# Arduino_extension_connectors.net
KiCad netlist of a schematic drawn in Altium Designer
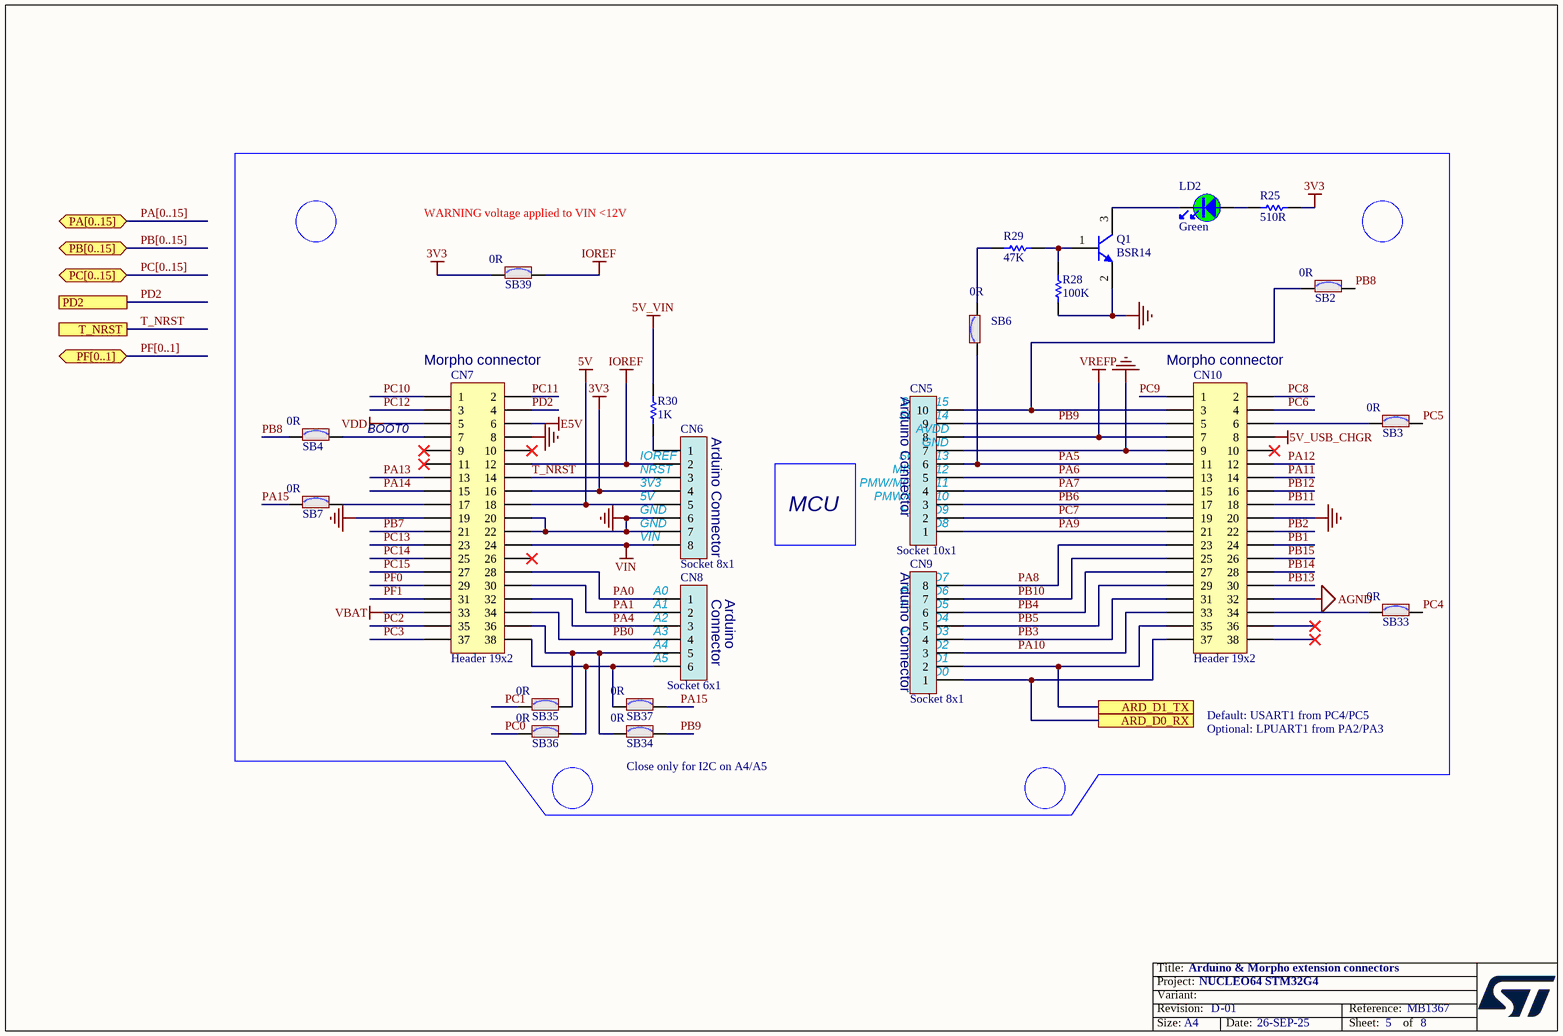
[diagram p0: Arduino_extension_connectors.SchDoc]

(export (version "E")
  (design (tool "Eeschema 10.0.6"))
  (components
    (comp (ref "CN5")
      (value "Socket 10x1")
      (footprint "CON_SAMTEC_SSW-110-03-X-S")
      (description "Socket, 10x1, 2.54mm, VR, TH, Height 8.51mm/10mm")
      (fields
        (field (name "INTERNAL_PART_NUMBER") "MCD-00262")
        (field (name "MANUFACTURER_PART_NUMBER") "SSW-110-03-G-S")
        (field (name "PROVIDED_BY") "SUBCO")
      )
      (libsource (lib "MCD_PARTS_database") (part "Socket 10x1"))
    )
    (comp (ref "CN6")
      (value "Socket 8x1")
      (footprint "CON_SAMTEC_SSW-108-03-X-S")
      (description "Socket, 8x1, 2.54mm, VR, TH, Height 8.51mm/10mm")
      (fields
        (field (name "INTERNAL_PART_NUMBER") "MCD-00261")
        (field (name "MANUFACTURER_PART_NUMBER") "SSW-108-03-G-S")
        (field (name "PROVIDED_BY") "SUBCO")
      )
      (libsource (lib "") (part "Socket 8x1_1"))
    )
    (comp (ref "CN7")
      (value "Header 19x2")
      (footprint "CON_SAMTEC_TSW-119-09-X-D")
      (description "Header, 19x2, 2,54mm, VR, TH, Height 5.84mm/10.16mm")
      (fields
        (field (name "INTERNAL_PART_NUMBER") "MCD-00213")
        (field (name "MANUFACTURER_PART_NUMBER") "TSW-119-09-G-D")
        (field (name "PROVIDED_BY") "SUBCO")
      )
      (libsource (lib "MCD_PARTS_database") (part "Header 19x2"))
    )
    (comp (ref "CN8")
      (value "Socket 6x1")
      (footprint "CON_SAMTEC_SSW-106-03-X-S")
      (description "Socket, 6x1, 2.54mm, VR, TH, Height 8.51mm/10mm")
      (fields
        (field (name "INTERNAL_PART_NUMBER") "MCD-00260")
        (field (name "MANUFACTURER_PART_NUMBER") "SSW-106-03-G-S")
        (field (name "PROVIDED_BY") "SUBCO")
      )
      (libsource (lib "MCD_PARTS_database") (part "Socket 6x1"))
    )
    (comp (ref "CN9")
      (value "Socket 8x1")
      (footprint "CON_SAMTEC_SSW-108-03-X-S")
      (description "Socket, 8x1, 2.54mm, VR, TH, Height 8.51mm/10mm")
      (fields
        (field (name "INTERNAL_PART_NUMBER") "MCD-00261")
        (field (name "MANUFACTURER_PART_NUMBER") "SSW-108-03-G-S")
        (field (name "PROVIDED_BY") "SUBCO")
      )
      (libsource (lib "MCD_PARTS_database") (part "Socket 8x1"))
    )
    (comp (ref "CN10")
      (value "Header 19x2")
      (footprint "CON_SAMTEC_TSW-119-09-X-D")
      (description "Header, 19x2, 2,54mm, VR, TH, Height 5.84mm/10.16mm")
      (fields
        (field (name "INTERNAL_PART_NUMBER") "MCD-00213")
        (field (name "MANUFACTURER_PART_NUMBER") "TSW-119-09-G-D")
        (field (name "PROVIDED_BY") "SUBCO")
      )
      (libsource (lib "MCD_PARTS_database") (part "Header 19x2"))
    )
    (comp (ref "LD2")
      (value "Green")
      (footprint "LED_0603_GREEN")
      (description "LED, Green, 2V, 20mA, 0603")
      (fields (field (name "INTERNAL_PART_NUMBER") "MCD-02900") (field (name "MANUFACTURER") "EVERLIGHT"))
      (libsource (lib "MCD_PARTS_database") (part "LED_green"))
    )
    (comp (ref "Q1")
      (value "BSR14")
      (footprint "NPN_SOT23")
      (description "NPN Bipolar Transistor")
      (fields
        (field (name "INTERNAL_PART_NUMBER") "MCD-00073")
        (field (name "MANUFACTURER") "ON SEMICONDUCTOR")
        (field (name "PROVIDED_BY") "SUBCO")
      )
      (libsource (lib "MCD_PARTS_database") (part "9013-SOT23"))
    )
    (comp (ref "R25")
      (value "510R")
      (footprint "R0603")
      (description "Resistor,510R,0603,1%,1/10W")
      (fields
        (field (name "INTERNAL_PART_NUMBER") "MCD-00225")
        (field (name "MANUFACTURER_PART_NUMBER") "RC0603FR-07510RL")
        (field (name "PROVIDED_BY") "SUBCO")
      )
      (libsource (lib "MCD_PARTS_database") (part "Resistor"))
    )
    (comp (ref "R28")
      (value "100K")
      (footprint "R0603")
      (description "Resistor,100K,0603,1%,1/10W")
      (fields
        (field (name "INTERNAL_PART_NUMBER") "MCD-00223")
        (field (name "MANUFACTURER_PART_NUMBER") "RC0603FR-07100KL")
        (field (name "PROVIDED_BY") "Subcon")
      )
      (libsource (lib "MCD_PARTS_database") (part "Resistor"))
    )
    (comp (ref "R29")
      (value "47K")
      (footprint "R0603")
      (description "Resistor,47K,0603,1%,1/10W")
      (fields
        (field (name "INTERNAL_PART_NUMBER") "MCD-00222")
        (field (name "MANUFACTURER_PART_NUMBER") "RC0603FR-0747KL")
        (field (name "PROVIDED_BY") "SUBCO")
      )
      (libsource (lib "MCD_PARTS_database") (part "Resistor"))
    )
    (comp (ref "R30")
      (value "1K")
      (footprint "R0603")
      (description "Resistor,1K,0603,1%,1/10W")
      (fields
        (field (name "INTERNAL_PART_NUMBER") "MCD-00070")
        (field (name "MANUFACTURER_PART_NUMBER") "RC0603FR-071KL")
        (field (name "PROVIDED_BY") "Subcon")
      )
      (libsource (lib "MCD_PARTS_database") (part "Resistor"))
    )
    (comp (ref "SB2")
      (value "0R")
      (footprint "SOLDER-BRIDGE_R0603-0R")
      (description "Solder Bridge ON")
      (fields
        (field (name "INTERNAL_PART_NUMBER") "MCD-00071")
        (field (name "MANUFACTURER_PART_NUMBER") "RC0603JR-070RL")
        (field (name "PROVIDED_BY") "SUBCO")
      )
      (libsource (lib "MCD_PARTS_database") (part "SB_ON"))
    )
    (comp (ref "SB3")
      (value "0R")
      (footprint "SOLDER-BRIDGE_R0603-0R")
      (description "Solder Bridge ON")
      (fields
        (field (name "INTERNAL_PART_NUMBER") "MCD-00071")
        (field (name "MANUFACTURER_PART_NUMBER") "RC0603JR-070RL")
        (field (name "PROVIDED_BY") "SUBCO")
      )
      (libsource (lib "MCD_PARTS_database") (part "SB_ON"))
    )
    (comp (ref "SB4")
      (value "0R")
      (footprint "SOLDER-BRIDGE_R0603-0R")
      (description "Solder Bridge ON")
      (fields
        (field (name "INTERNAL_PART_NUMBER") "MCD-00071")
        (field (name "MANUFACTURER_PART_NUMBER") "RC0603JR-070RL")
        (field (name "PROVIDED_BY") "SUBCO")
      )
      (libsource (lib "MCD_PARTS_database") (part "SB_ON"))
    )
    (comp (ref "SB6")
      (value "0R")
      (footprint "SOLDER-BRIDGE_R0603-0R")
      (description "Solder Bridge ON")
      (fields
        (field (name "INTERNAL_PART_NUMBER") "MCD-00071")
        (field (name "MANUFACTURER_PART_NUMBER") "RC0603JR-070RL")
        (field (name "PROVIDED_BY") "SUBCO")
      )
      (libsource (lib "") (part "SB_ON_1"))
    )
    (comp (ref "SB7")
      (value "0R")
      (footprint "SOLDER-BRIDGE_R0603-0R")
      (description "Solder Bridge ON")
      (fields
        (field (name "INTERNAL_PART_NUMBER") "MCD-00071")
        (field (name "MANUFACTURER_PART_NUMBER") "RC0603JR-070RL")
        (field (name "PROVIDED_BY") "SUBCO")
      )
      (libsource (lib "MCD_PARTS_database") (part "SB_ON"))
    )
    (comp (ref "SB33")
      (value "0R")
      (footprint "SOLDER-BRIDGE_R0603-0R")
      (description "Solder Bridge ON")
      (fields
        (field (name "INTERNAL_PART_NUMBER") "MCD-00071")
        (field (name "MANUFACTURER_PART_NUMBER") "RC0603JR-070RL")
        (field (name "PROVIDED_BY") "SUBCO")
      )
      (libsource (lib "MCD_PARTS_database") (part "SB_ON"))
    )
    (comp (ref "SB34")
      (value "0R")
      (footprint "SOLDER-BRIDGE_R0603-0R")
      (description "Solder Bridge ON")
      (fields
        (field (name "INTERNAL_PART_NUMBER") "MCD-00071")
        (field (name "MANUFACTURER_PART_NUMBER") "RC0603JR-070RL")
        (field (name "PROVIDED_BY") "SUBCO")
      )
      (libsource (lib "MCD_PARTS_database") (part "SB_ON"))
    )
    (comp (ref "SB35")
      (value "0R")
      (footprint "SOLDER-BRIDGE_R0603-0R")
      (description "Solder Bridge ON")
      (fields
        (field (name "INTERNAL_PART_NUMBER") "MCD-00071")
        (field (name "MANUFACTURER_PART_NUMBER") "RC0603JR-070RL")
        (field (name "PROVIDED_BY") "SUBCO")
      )
      (libsource (lib "MCD_PARTS_database") (part "SB_ON"))
    )
    (comp (ref "SB36")
      (value "0R")
      (footprint "SOLDER-BRIDGE_R0603-0R")
      (description "Solder Bridge ON")
      (fields
        (field (name "INTERNAL_PART_NUMBER") "MCD-00071")
        (field (name "MANUFACTURER_PART_NUMBER") "RC0603JR-070RL")
        (field (name "PROVIDED_BY") "SUBCO")
      )
      (libsource (lib "MCD_PARTS_database") (part "SB_ON"))
    )
    (comp (ref "SB37")
      (value "0R")
      (footprint "SOLDER-BRIDGE_R0603-0R")
      (description "Solder Bridge ON")
      (fields
        (field (name "INTERNAL_PART_NUMBER") "MCD-00071")
        (field (name "MANUFACTURER_PART_NUMBER") "RC0603JR-070RL")
        (field (name "PROVIDED_BY") "SUBCO")
      )
      (libsource (lib "MCD_PARTS_database") (part "SB_ON"))
    )
    (comp (ref "SB39")
      (value "0R")
      (footprint "SOLDER-BRIDGE_R0603-0R")
      (description "Solder Bridge ON")
      (fields
        (field (name "INTERNAL_PART_NUMBER") "MCD-00071")
        (field (name "MANUFACTURER_PART_NUMBER") "RC0603JR-070RL")
        (field (name "PROVIDED_BY") "SUBCO")
      )
      (libsource (lib "MCD_PARTS_database") (part "SB_ON"))
    )
  )
  (nets
    (net (code "3") (name "/ARD_D0_RX") (class "Default")
      (node (ref "CN10") (pin "37") (pinfunction "37_37") (pintype "passive"))
      (node (ref "CN9") (pin "1") (pinfunction "1_1") (pintype "passive"))
    )
    (net (code "4") (name "/ARD_D1_TX") (class "Default")
      (node (ref "CN10") (pin "35") (pinfunction "35_35") (pintype "passive"))
      (node (ref "CN9") (pin "2") (pinfunction "2_2") (pintype "passive"))
    )
    (net (code "5") (name "/PA0") (class "Default")
      (node (ref "CN7") (pin "28") (pinfunction "28_28") (pintype "passive"))
      (node (ref "CN8") (pin "1") (pinfunction "1_1") (pintype "passive"))
    )
    (net (code "6") (name "/PA1") (class "Default")
      (node (ref "CN7") (pin "30") (pinfunction "30_30") (pintype "passive"))
      (node (ref "CN8") (pin "2") (pinfunction "2_2") (pintype "passive"))
    )
    (net (code "7") (name "/PA4") (class "Default")
      (node (ref "CN7") (pin "32") (pinfunction "32_32") (pintype "passive"))
      (node (ref "CN8") (pin "3") (pinfunction "3_3") (pintype "passive"))
    )
    (net (code "8") (name "/PA5") (class "Default")
      (node (ref "CN10") (pin "11") (pinfunction "11_11") (pintype "passive"))
      (node (ref "CN5") (pin "6") (pinfunction "6_6") (pintype "passive"))
      (node (ref "SB6") (pin "1") (pinfunction "1_1") (pintype "passive"))
    )
    (net (code "9") (name "/PA6") (class "Default")
      (node (ref "CN10") (pin "13") (pinfunction "13_13") (pintype "passive"))
      (node (ref "CN5") (pin "5") (pinfunction "5_5") (pintype "passive"))
    )
    (net (code "10") (name "/PA7") (class "Default")
      (node (ref "CN10") (pin "15") (pinfunction "15_15") (pintype "passive"))
      (node (ref "CN5") (pin "4") (pinfunction "4_4") (pintype "passive"))
    )
    (net (code "11") (name "/PA8") (class "Default")
      (node (ref "CN10") (pin "23") (pinfunction "23_23") (pintype "passive"))
      (node (ref "CN9") (pin "8") (pinfunction "8_8") (pintype "passive"))
    )
    (net (code "12") (name "/PA9") (class "Default")
      (node (ref "CN10") (pin "21") (pinfunction "21_21") (pintype "passive"))
      (node (ref "CN5") (pin "1") (pinfunction "1_1") (pintype "passive"))
    )
    (net (code "13") (name "/PA10") (class "Default")
      (node (ref "CN10") (pin "33") (pinfunction "33_33") (pintype "passive"))
      (node (ref "CN9") (pin "3") (pinfunction "3_3") (pintype "passive"))
    )
    (net (code "14") (name "/PA11") (class "Default")
      (node (ref "CN10") (pin "14") (pinfunction "14_14") (pintype "passive"))
    )
    (net (code "15") (name "/PA12") (class "Default")
      (node (ref "CN10") (pin "12") (pinfunction "12_12") (pintype "passive"))
    )
    (net (code "16") (name "/PA13") (class "Default")
      (node (ref "CN7") (pin "13") (pinfunction "13_13") (pintype "passive"))
    )
    (net (code "17") (name "/PA14") (class "Default")
      (node (ref "CN7") (pin "15") (pinfunction "15_15") (pintype "passive"))
    )
    (net (code "18") (name "/PA15") (class "Default")
      (node (ref "SB37") (pin "2") (pinfunction "2_2") (pintype "passive"))
      (node (ref "SB7") (pin "1") (pinfunction "1_1") (pintype "passive"))
    )
    (net (code "20") (name "/PB0") (class "Default")
      (node (ref "CN7") (pin "34") (pinfunction "34_34") (pintype "passive"))
      (node (ref "CN8") (pin "4") (pinfunction "4_4") (pintype "passive"))
    )
    (net (code "21") (name "/PB1") (class "Default")
      (node (ref "CN10") (pin "24") (pinfunction "24_24") (pintype "passive"))
    )
    (net (code "22") (name "/PB2") (class "Default")
      (node (ref "CN10") (pin "22") (pinfunction "22_22") (pintype "passive"))
    )
    (net (code "23") (name "/PB3") (class "Default")
      (node (ref "CN10") (pin "31") (pinfunction "31_31") (pintype "passive"))
      (node (ref "CN9") (pin "4") (pinfunction "4_4") (pintype "passive"))
    )
    (net (code "24") (name "/PB4") (class "Default")
      (node (ref "CN10") (pin "27") (pinfunction "27_27") (pintype "passive"))
      (node (ref "CN9") (pin "6") (pinfunction "6_6") (pintype "passive"))
    )
    (net (code "25") (name "/PB5") (class "Default")
      (node (ref "CN10") (pin "29") (pinfunction "29_29") (pintype "passive"))
      (node (ref "CN9") (pin "5") (pinfunction "5_5") (pintype "passive"))
    )
    (net (code "26") (name "/PB6") (class "Default")
      (node (ref "CN10") (pin "17") (pinfunction "17_17") (pintype "passive"))
      (node (ref "CN5") (pin "3") (pinfunction "3_3") (pintype "passive"))
    )
    (net (code "27") (name "/PB7") (class "Default")
      (node (ref "CN7") (pin "21") (pinfunction "21_21") (pintype "passive"))
    )
    (net (code "28") (name "/PB8") (class "Default")
      (node (ref "SB2") (pin "2") (pinfunction "2_2") (pintype "passive"))
      (node (ref "SB4") (pin "1") (pinfunction "1_1") (pintype "passive"))
    )
    (net (code "29") (name "/PB9") (class "Default")
      (node (ref "CN10") (pin "5") (pinfunction "5_5") (pintype "passive"))
      (node (ref "CN5") (pin "9") (pinfunction "9_9") (pintype "passive"))
      (node (ref "SB34") (pin "2") (pinfunction "2_2") (pintype "passive"))
    )
    (net (code "30") (name "/PB10") (class "Default")
      (node (ref "CN10") (pin "25") (pinfunction "25_25") (pintype "passive"))
      (node (ref "CN9") (pin "7") (pinfunction "7_7") (pintype "passive"))
    )
    (net (code "31") (name "/PB11") (class "Default")
      (node (ref "CN10") (pin "18") (pinfunction "18_18") (pintype "passive"))
    )
    (net (code "32") (name "/PB12") (class "Default")
      (node (ref "CN10") (pin "16") (pinfunction "16_16") (pintype "passive"))
    )
    (net (code "33") (name "/PB13") (class "Default")
      (node (ref "CN10") (pin "30") (pinfunction "30_30") (pintype "passive"))
    )
    (net (code "34") (name "/PB14") (class "Default")
      (node (ref "CN10") (pin "28") (pinfunction "28_28") (pintype "passive"))
    )
    (net (code "35") (name "/PB15") (class "Default")
      (node (ref "CN10") (pin "26") (pinfunction "26_26") (pintype "passive"))
    )
    (net (code "37") (name "/PC0") (class "Default")
      (node (ref "SB36") (pin "1") (pinfunction "1_1") (pintype "passive"))
    )
    (net (code "38") (name "/PC1") (class "Default")
      (node (ref "SB35") (pin "1") (pinfunction "1_1") (pintype "passive"))
    )
    (net (code "39") (name "/PC2") (class "Default")
      (node (ref "CN7") (pin "35") (pinfunction "35_35") (pintype "passive"))
    )
    (net (code "40") (name "/PC3") (class "Default")
      (node (ref "CN7") (pin "37") (pinfunction "37_37") (pintype "passive"))
    )
    (net (code "41") (name "/PC4") (class "Default")
      (node (ref "SB33") (pin "2") (pinfunction "2_2") (pintype "passive"))
    )
    (net (code "42") (name "/PC5") (class "Default")
      (node (ref "SB3") (pin "2") (pinfunction "2_2") (pintype "passive"))
    )
    (net (code "43") (name "/PC6") (class "Default")
      (node (ref "CN10") (pin "4") (pinfunction "4_4") (pintype "passive"))
    )
    (net (code "44") (name "/PC7") (class "Default")
      (node (ref "CN10") (pin "19") (pinfunction "19_19") (pintype "passive"))
      (node (ref "CN5") (pin "2") (pinfunction "2_2") (pintype "passive"))
    )
    (net (code "45") (name "/PC8") (class "Default")
      (node (ref "CN10") (pin "2") (pinfunction "2_2") (pintype "passive"))
    )
    (net (code "46") (name "/PC9") (class "Default")
      (node (ref "CN10") (pin "1") (pinfunction "1_1") (pintype "passive"))
    )
    (net (code "47") (name "/PC10") (class "Default")
      (node (ref "CN7") (pin "1") (pinfunction "1_1") (pintype "passive"))
    )
    (net (code "48") (name "/PC11") (class "Default")
      (node (ref "CN7") (pin "2") (pinfunction "2_2") (pintype "passive"))
    )
    (net (code "49") (name "/PC12") (class "Default")
      (node (ref "CN7") (pin "3") (pinfunction "3_3") (pintype "passive"))
    )
    (net (code "50") (name "/PC13") (class "Default")
      (node (ref "CN7") (pin "23") (pinfunction "23_23") (pintype "passive"))
    )
    (net (code "51") (name "/PC14") (class "Default")
      (node (ref "CN7") (pin "25") (pinfunction "25_25") (pintype "passive"))
    )
    (net (code "52") (name "/PC15") (class "Default")
      (node (ref "CN7") (pin "27") (pinfunction "27_27") (pintype "passive"))
    )
    (net (code "54") (name "/PD2") (class "Default")
      (node (ref "CN7") (pin "4") (pinfunction "4_4") (pintype "passive"))
    )
    (net (code "55") (name "/PF0") (class "Default")
      (node (ref "CN7") (pin "29") (pinfunction "29_29") (pintype "passive"))
    )
    (net (code "56") (name "/PF1") (class "Default")
      (node (ref "CN7") (pin "31") (pinfunction "31_31") (pintype "passive"))
    )
    (net (code "58") (name "/T_NRST") (class "Default")
      (node (ref "CN6") (pin "3") (pinfunction "3_3") (pintype "passive"))
      (node (ref "CN7") (pin "14") (pinfunction "14_14") (pintype "passive"))
    )
    (net (code "59") (name "3V3") (class "Default")
      (node (ref "CN6") (pin "4") (pinfunction "4_4") (pintype "passive"))
      (node (ref "CN7") (pin "16") (pinfunction "16_16") (pintype "passive"))
      (node (ref "R25") (pin "1") (pinfunction "1_1") (pintype "passive"))
      (node (ref "SB39") (pin "1") (pinfunction "1_1") (pintype "passive"))
    )
    (net (code "60") (name "5V") (class "Default")
      (node (ref "CN6") (pin "5") (pinfunction "5_5") (pintype "passive"))
      (node (ref "CN7") (pin "18") (pinfunction "18_18") (pintype "passive"))
    )
    (net (code "61") (name "5V_USB_CHGR") (class "Default")
      (node (ref "CN10") (pin "8") (pinfunction "8_8") (pintype "passive"))
    )
    (net (code "62") (name "5V_VIN") (class "Default")
      (node (ref "R30") (pin "2") (pinfunction "2_2") (pintype "passive"))
    )
    (net (code "63") (name "AGND") (class "Default")
      (node (ref "CN10") (pin "32") (pinfunction "32_32") (pintype "passive"))
    )
    (net (code "64") (name "E5V") (class "Default")
      (node (ref "CN7") (pin "6") (pinfunction "6_6") (pintype "passive"))
    )
    (net (code "65") (name "GND") (class "Default")
      (node (ref "CN10") (pin "20") (pinfunction "20_20") (pintype "passive"))
      (node (ref "CN10") (pin "9") (pinfunction "9_9") (pintype "passive"))
      (node (ref "CN5") (pin "7") (pinfunction "7_7") (pintype "passive"))
      (node (ref "CN6") (pin "6") (pinfunction "6_6") (pintype "passive"))
      (node (ref "CN6") (pin "7") (pinfunction "7_7") (pintype "passive"))
      (node (ref "CN7") (pin "19") (pinfunction "19_19") (pintype "passive"))
      (node (ref "CN7") (pin "20") (pinfunction "20_20") (pintype "passive"))
      (node (ref "CN7") (pin "22") (pinfunction "22_22") (pintype "passive"))
      (node (ref "CN7") (pin "8") (pinfunction "8_8") (pintype "passive"))
      (node (ref "Q1") (pin "2") (pinfunction "E_2") (pintype "passive"))
      (node (ref "R28") (pin "1") (pinfunction "1_1") (pintype "passive"))
    )
    (net (code "66") (name "IOREF") (class "Default")
      (node (ref "CN6") (pin "2") (pinfunction "2_2") (pintype "passive"))
      (node (ref "CN7") (pin "12") (pinfunction "12_12") (pintype "passive"))
      (node (ref "SB39") (pin "2") (pinfunction "2_2") (pintype "passive"))
    )
    (net (code "67") (name "Net-(CN6-Pad1)") (class "Default")
      (node (ref "CN6") (pin "1") (pinfunction "1_1") (pintype "passive"))
      (node (ref "R30") (pin "1") (pinfunction "1_1") (pintype "passive"))
    )
    (net (code "68") (name "Net-(CN7-Pad7)") (class "Default")
      (node (ref "CN7") (pin "7") (pinfunction "7_7") (pintype "passive"))
      (node (ref "SB4") (pin "2") (pinfunction "2_2") (pintype "passive"))
    )
    (net (code "69") (name "Net-(CN7-Pad17)") (class "Default")
      (node (ref "CN7") (pin "17") (pinfunction "17_17") (pintype "passive"))
      (node (ref "SB7") (pin "2") (pinfunction "2_2") (pintype "passive"))
    )
    (net (code "70") (name "Net-(CN7-Pad36)") (class "Default")
      (node (ref "CN7") (pin "36") (pinfunction "36_36") (pintype "passive"))
      (node (ref "CN8") (pin "5") (pinfunction "5_5") (pintype "passive"))
      (node (ref "SB34") (pin "1") (pinfunction "1_1") (pintype "passive"))
      (node (ref "SB35") (pin "2") (pinfunction "2_2") (pintype "passive"))
    )
    (net (code "71") (name "Net-(CN7-Pad38)") (class "Default")
      (node (ref "CN7") (pin "38") (pinfunction "38_38") (pintype "passive"))
      (node (ref "CN8") (pin "6") (pinfunction "6_6") (pintype "passive"))
      (node (ref "SB36") (pin "2") (pinfunction "2_2") (pintype "passive"))
      (node (ref "SB37") (pin "1") (pinfunction "1_1") (pintype "passive"))
    )
    (net (code "72") (name "Net-(CN10-Pad3)") (class "Default")
      (node (ref "CN10") (pin "3") (pinfunction "3_3") (pintype "passive"))
      (node (ref "CN5") (pin "10") (pinfunction "10_10") (pintype "passive"))
      (node (ref "SB2") (pin "1") (pinfunction "1_1") (pintype "passive"))
    )
    (net (code "73") (name "Net-(CN10-Pad6)") (class "Default")
      (node (ref "CN10") (pin "6") (pinfunction "6_6") (pintype "passive"))
      (node (ref "SB3") (pin "1") (pinfunction "1_1") (pintype "passive"))
    )
    (net (code "74") (name "Net-(CN10-Pad34)") (class "Default")
      (node (ref "CN10") (pin "34") (pinfunction "34_34") (pintype "passive"))
      (node (ref "SB33") (pin "1") (pinfunction "1_1") (pintype "passive"))
    )
    (net (code "75") (name "Net-(LD2-Pad1)") (class "Default")
      (node (ref "LD2") (pin "1") (pintype "passive"))
      (node (ref "R25") (pin "2") (pinfunction "2_2") (pintype "passive"))
    )
    (net (code "76") (name "Net-(Q1-B)") (class "Default")
      (node (ref "Q1") (pin "1") (pinfunction "B_1") (pintype "passive"))
      (node (ref "R28") (pin "2") (pinfunction "2_2") (pintype "passive"))
      (node (ref "R29") (pin "2") (pinfunction "2_2") (pintype "passive"))
    )
    (net (code "77") (name "Net-(Q1-C)") (class "Default")
      (node (ref "LD2") (pin "2") (pintype "passive"))
      (node (ref "Q1") (pin "3") (pinfunction "C_3") (pintype "passive"))
    )
    (net (code "78") (name "Net-(R29-Pad1)") (class "Default")
      (node (ref "R29") (pin "1") (pinfunction "1_1") (pintype "passive"))
      (node (ref "SB6") (pin "2") (pinfunction "2_2") (pintype "passive"))
    )
    (net (code "79") (name "VBAT") (class "Default")
      (node (ref "CN7") (pin "33") (pinfunction "33_33") (pintype "passive"))
    )
    (net (code "80") (name "VDD") (class "Default")
      (node (ref "CN7") (pin "5") (pinfunction "5_5") (pintype "passive"))
    )
    (net (code "81") (name "VIN") (class "Default")
      (node (ref "CN6") (pin "8") (pinfunction "8_8") (pintype "passive"))
      (node (ref "CN7") (pin "24") (pinfunction "24_24") (pintype "passive"))
    )
    (net (code "82") (name "VREFP") (class "Default")
      (node (ref "CN10") (pin "7") (pinfunction "7_7") (pintype "passive"))
      (node (ref "CN5") (pin "8") (pinfunction "8_8") (pintype "passive"))
    )
    (net (code "83") (name "unconnected-(CN7-Pad9)") (class "Default")
      (node (ref "CN7") (pin "9") (pinfunction "9_9") (pintype "passive+no_connect"))
    )
    (net (code "84") (name "unconnected-(CN7-Pad10)") (class "Default")
      (node (ref "CN7") (pin "10") (pinfunction "10_10") (pintype "passive+no_connect"))
    )
    (net (code "85") (name "unconnected-(CN7-Pad11)") (class "Default")
      (node (ref "CN7") (pin "11") (pinfunction "11_11") (pintype "passive+no_connect"))
    )
    (net (code "86") (name "unconnected-(CN7-Pad26)") (class "Default")
      (node (ref "CN7") (pin "26") (pinfunction "26_26") (pintype "passive+no_connect"))
    )
    (net (code "87") (name "unconnected-(CN10-Pad10)") (class "Default")
      (node (ref "CN10") (pin "10") (pinfunction "10_10") (pintype "passive+no_connect"))
    )
    (net (code "88") (name "unconnected-(CN10-Pad36)") (class "Default")
      (node (ref "CN10") (pin "36") (pinfunction "36_36") (pintype "passive+no_connect"))
    )
    (net (code "89") (name "unconnected-(CN10-Pad38)") (class "Default")
      (node (ref "CN10") (pin "38") (pinfunction "38_38") (pintype "passive+no_connect"))
    )
  )
)
